# RT1064_Power.net
KiCad netlist of a schematic drawn in Altium Designer
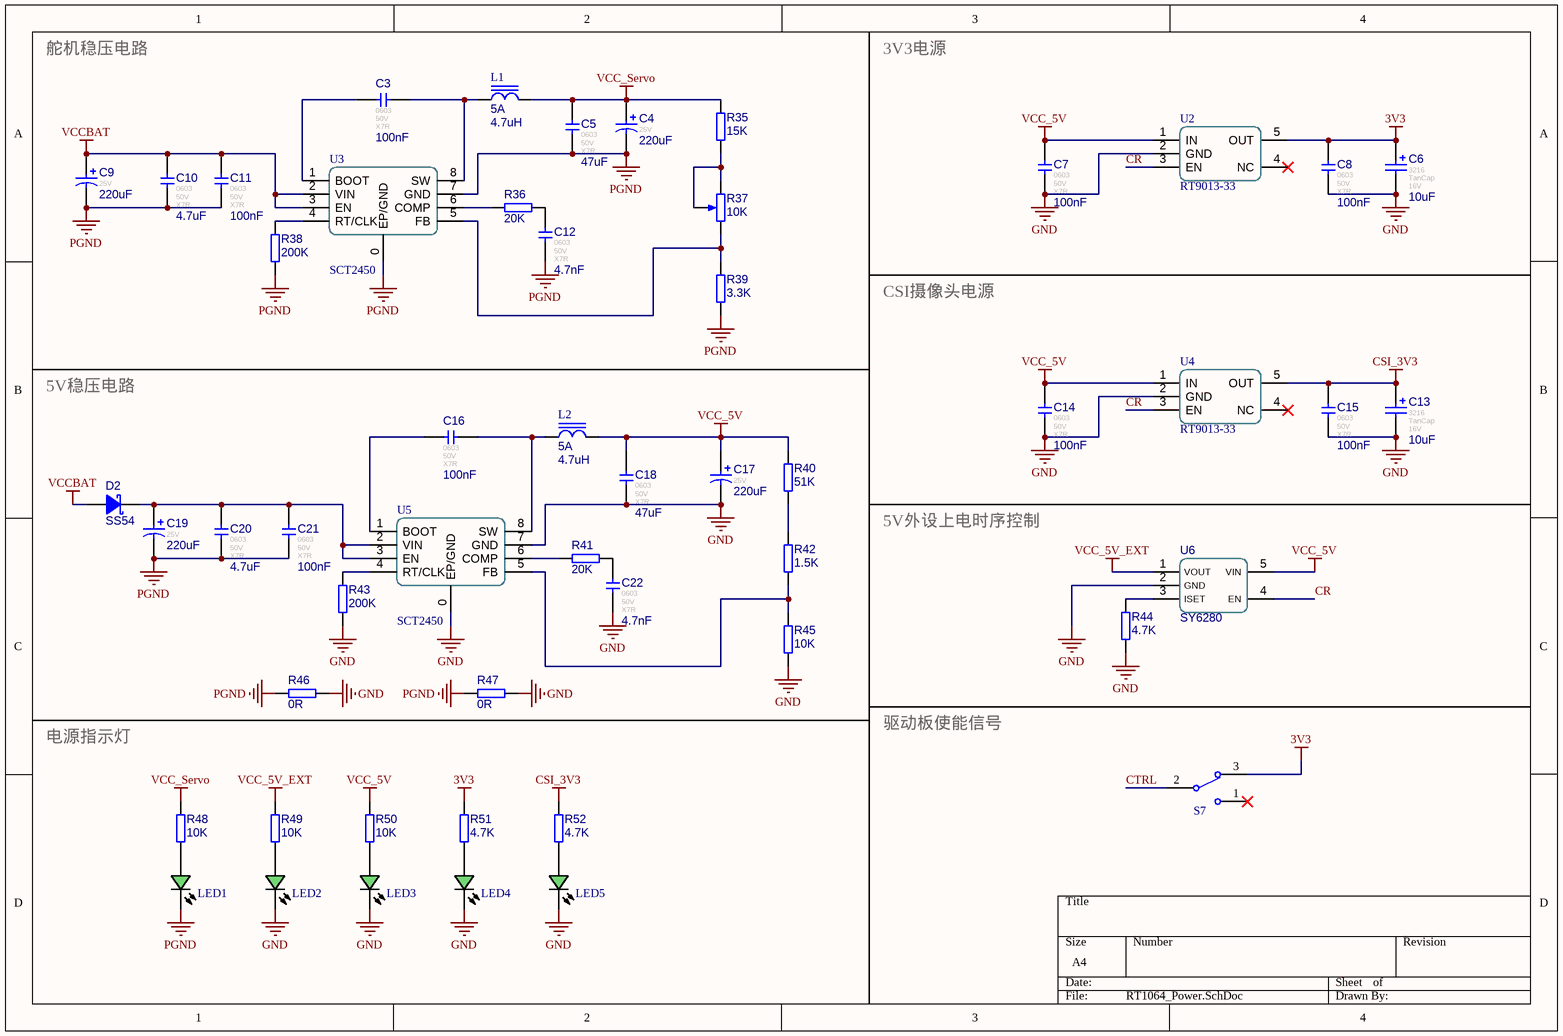
[diagram p0: RT1064_Power.SchDoc]

(export (version "E")
  (design (tool "Eeschema 10.0.6"))
  (components
    (comp (ref "C3")
      (value "100nF")
      (footprint "0603")
      (description "贴片瓷片电容; MLCC; 0603(1608);")
      (fields
        (field (name "VOLTAGE") "50V")
        (field (name "TYPE") "X7R")
        (field (name "Comment") "100nF 50V X7R")
      )
      (libsource (lib "RT1064_V1主板器件封装集成库") (part "100nF 0603 50V X7R"))
    )
    (comp (ref "C4")
      (value "220uF")
      (footprint "CAP-E-S 6.3")
      (description "贴片电解电容 220uF 25V 6.3x7.7")
      (fields (field (name "VOLTAGE") "25V") (field (name "Comment") "220uF 25V 铝电解"))
      (libsource (lib "RT1064_V1主板器件封装集成库") (part "E-S 220uF 25V 6.3x7.7"))
    )
    (comp (ref "C5")
      (value "47uF")
      (footprint "0603")
      (description "贴片瓷片电容; MLCC; 0603(1608);")
      (fields
        (field (name "VOLTAGE") "50V")
        (field (name "TYPE") "X7R")
        (field (name "Comment") "47uF 50V X7R")
      )
      (libsource (lib "RT1064_V1主板器件封装集成库") (part "100nF 0603 50V X7R"))
    )
    (comp (ref "C6")
      (value "10uF")
      (footprint "3216")
      (description "贴片钽电容 10uF 3216 16V")
      (fields
        (field (name "TYPE") "TanCap")
        (field (name "VOLTAGE") "16V")
        (field (name "Comment") "T-S 10uF 3216 16V")
      )
      (libsource (lib "RT1064_V1主板器件封装集成库") (part "T-S 10uF 3216 16V"))
    )
    (comp (ref "C7")
      (value "100nF")
      (footprint "0603")
      (description "贴片瓷片电容; MLCC; 0603(1608);")
      (fields
        (field (name "VOLTAGE") "50V")
        (field (name "TYPE") "X7R")
        (field (name "Comment") "100nF 50V X7R")
      )
      (libsource (lib "RT1064_V1主板器件封装集成库") (part "100nF 0603 50V X7R"))
    )
    (comp (ref "C8")
      (value "100nF")
      (footprint "0603")
      (description "贴片瓷片电容; MLCC; 0603(1608);")
      (fields
        (field (name "VOLTAGE") "50V")
        (field (name "TYPE") "X7R")
        (field (name "Comment") "100nF 50V X7R")
      )
      (libsource (lib "RT1064_V1主板器件封装集成库") (part "100nF 0603 50V X7R"))
    )
    (comp (ref "C9")
      (value "220uF")
      (footprint "CAP-E-S 6.3")
      (description "贴片电解电容 220uF 25V 6.3x7.7")
      (fields (field (name "VOLTAGE") "25V") (field (name "Comment") "220uF 25V 铝电解"))
      (libsource (lib "RT1064_V1主板器件封装集成库") (part "E-S 220uF 25V 6.3x7.7"))
    )
    (comp (ref "C10")
      (value "4.7uF")
      (footprint "0603")
      (description "贴片瓷片电容; MLCC; 0603(1608);")
      (fields
        (field (name "VOLTAGE") "50V")
        (field (name "TYPE") "X7R")
        (field (name "Comment") "4.7uF 50V X7R")
      )
      (libsource (lib "RT1064_V1主板器件封装集成库") (part "100nF 0603 50V X7R"))
    )
    (comp (ref "C11")
      (value "100nF")
      (footprint "0603")
      (description "贴片瓷片电容; MLCC; 0603(1608);")
      (fields
        (field (name "VOLTAGE") "50V")
        (field (name "TYPE") "X7R")
        (field (name "Comment") "100nF 50V X7R")
      )
      (libsource (lib "RT1064_V1主板器件封装集成库") (part "100nF 0603 50V X7R"))
    )
    (comp (ref "C12")
      (value "4.7nF")
      (footprint "0603")
      (description "贴片瓷片电容; MLCC; 0603(1608);")
      (fields
        (field (name "VOLTAGE") "50V")
        (field (name "TYPE") "X7R")
        (field (name "Comment") "4.7nF 50V X7R")
      )
      (libsource (lib "RT1064_V1主板器件封装集成库") (part "4.7nF 0603 50V X7R"))
    )
    (comp (ref "C13")
      (value "10uF")
      (footprint "3216")
      (description "贴片钽电容 10uF 3216 16V")
      (fields
        (field (name "TYPE") "TanCap")
        (field (name "VOLTAGE") "16V")
        (field (name "Comment") "T-S 10uF 3216 16V")
      )
      (libsource (lib "RT1064_V1主板器件封装集成库") (part "T-S 10uF 3216 16V"))
    )
    (comp (ref "C14")
      (value "100nF")
      (footprint "0603")
      (description "贴片瓷片电容; MLCC; 0603(1608);")
      (fields
        (field (name "VOLTAGE") "50V")
        (field (name "TYPE") "X7R")
        (field (name "Comment") "100nF 50V X7R")
      )
      (libsource (lib "RT1064_V1主板器件封装集成库") (part "100nF 0603 50V X7R"))
    )
    (comp (ref "C15")
      (value "100nF")
      (footprint "0603")
      (description "贴片瓷片电容; MLCC; 0603(1608);")
      (fields
        (field (name "VOLTAGE") "50V")
        (field (name "TYPE") "X7R")
        (field (name "Comment") "100nF 50V X7R")
      )
      (libsource (lib "RT1064_V1主板器件封装集成库") (part "100nF 0603 50V X7R"))
    )
    (comp (ref "C16")
      (value "100nF")
      (footprint "0603")
      (description "贴片瓷片电容; MLCC; 0603(1608);")
      (fields
        (field (name "VOLTAGE") "50V")
        (field (name "TYPE") "X7R")
        (field (name "Comment") "100nF 50V X7R")
      )
      (libsource (lib "RT1064_V1主板器件封装集成库") (part "100nF 0603 50V X7R"))
    )
    (comp (ref "C17")
      (value "220uF")
      (footprint "CAP-E-S 6.3")
      (description "贴片电解电容 220uF 25V 6.3x7.7")
      (fields (field (name "VOLTAGE") "25V") (field (name "Comment") "220uF 25V 铝电解"))
      (libsource (lib "RT1064_V1主板器件封装集成库") (part "E-S 220uF 25V 6.3x7.7"))
    )
    (comp (ref "C18")
      (value "47uF")
      (footprint "0603")
      (description "贴片瓷片电容; MLCC; 0603(1608);")
      (fields
        (field (name "VOLTAGE") "50V")
        (field (name "TYPE") "X7R")
        (field (name "Comment") "47uF 50V X7R")
      )
      (libsource (lib "RT1064_V1主板器件封装集成库") (part "100nF 0603 50V X7R"))
    )
    (comp (ref "C19")
      (value "220uF")
      (footprint "CAP-E-S 6.3")
      (description "贴片电解电容 220uF 25V 6.3x7.7")
      (fields (field (name "VOLTAGE") "25V") (field (name "Comment") "220uF 25V 铝电解"))
      (libsource (lib "RT1064_V1主板器件封装集成库") (part "E-S 220uF 25V 6.3x7.7"))
    )
    (comp (ref "C20")
      (value "4.7uF")
      (footprint "0603")
      (description "贴片瓷片电容; MLCC; 0603(1608);")
      (fields
        (field (name "VOLTAGE") "50V")
        (field (name "TYPE") "X7R")
        (field (name "Comment") "4.7uF 50V X7R")
      )
      (libsource (lib "RT1064_V1主板器件封装集成库") (part "100nF 0603 50V X7R"))
    )
    (comp (ref "C21")
      (value "100nF")
      (footprint "0603")
      (description "贴片瓷片电容; MLCC; 0603(1608);")
      (fields
        (field (name "VOLTAGE") "50V")
        (field (name "TYPE") "X7R")
        (field (name "Comment") "100nF 50V X7R")
      )
      (libsource (lib "RT1064_V1主板器件封装集成库") (part "100nF 0603 50V X7R"))
    )
    (comp (ref "C22")
      (value "4.7nF")
      (footprint "0603")
      (description "贴片瓷片电容; MLCC; 0603(1608);")
      (fields
        (field (name "VOLTAGE") "50V")
        (field (name "TYPE") "X7R")
        (field (name "Comment") "4.7nF 50V X7R")
      )
      (libsource (lib "RT1064_V1主板器件封装集成库") (part "4.7nF 0603 50V X7R"))
    )
    (comp (ref "D2")
      (value "SS54")
      (footprint "SMA-L[DO-214AC]")
      (description "SS54 肖特基二极管")
      (libsource (lib "RT1064_V1主板器件封装集成库") (part "SS54"))
    )
    (comp (ref "L1")
      (value "4.7uH")
      (footprint "0630 TPC 7*7*3")
      (description "功率电感")
      (fields
        (field (name "IMAX") "5A")
        (field (name "Comment") "4.7uH 5A")
        (field (name "PUBLISHER") "Altium Limited")
      )
      (libsource (lib "RT1064_V1主板器件封装集成库") (part "Ind-Power"))
    )
    (comp (ref "L2")
      (value "4.7uH")
      (footprint "0630 TPC 7*7*3")
      (description "功率电感")
      (fields
        (field (name "IMAX") "5A")
        (field (name "Comment") "4.7uH 5A")
        (field (name "PUBLISHER") "Altium Limited")
      )
      (libsource (lib "RT1064_V1主板器件封装集成库") (part "Ind-Power"))
    )
    (comp (ref "LED1")
      (value "翠绿贴片LED")
      (footprint "LEDC1608(0603)-L")
      (fields (field (name "PUBLISHER") "Altium Limited"))
      (libsource (lib "RT1064_V1主板器件封装集成库") (part "LED Chip Green"))
    )
    (comp (ref "LED2")
      (value "翠绿贴片LED")
      (footprint "LEDC1608(0603)-L")
      (fields (field (name "PUBLISHER") "Altium Limited"))
      (libsource (lib "RT1064_V1主板器件封装集成库") (part "LED Chip Green"))
    )
    (comp (ref "LED3")
      (value "翠绿贴片LED")
      (footprint "LEDC1608(0603)-L")
      (fields (field (name "PUBLISHER") "Altium Limited"))
      (libsource (lib "RT1064_V1主板器件封装集成库") (part "LED Chip Green"))
    )
    (comp (ref "LED4")
      (value "翠绿贴片LED")
      (footprint "LEDC1608(0603)-L")
      (fields (field (name "PUBLISHER") "Altium Limited"))
      (libsource (lib "RT1064_V1主板器件封装集成库") (part "LED Chip Green"))
    )
    (comp (ref "LED5")
      (value "翠绿贴片LED")
      (footprint "LEDC1608(0603)-L")
      (fields (field (name "PUBLISHER") "Altium Limited"))
      (libsource (lib "RT1064_V1主板器件封装集成库") (part "LED Chip Green"))
    )
    (comp (ref "R35")
      (value "15K")
      (footprint "RESC1608[0603]S-L")
      (description "贴片电阻")
      (fields (field (name "POWER") "1/8W") (field (name "TOLERANCE") "±1%"))
      (libsource (lib "RT1064_V1主板器件封装集成库") (part "Res-Chip"))
    )
    (comp (ref "R36")
      (value "20K")
      (footprint "RESC1608[0603]S-L")
      (description "贴片电阻")
      (fields (field (name "POWER") "1/8W") (field (name "TOLERANCE") "±1%"))
      (libsource (lib "RT1064_V1主板器件封装集成库") (part "Res-Chip"))
    )
    (comp (ref "R37")
      (value "10K")
      (footprint "RESPOT3296W")
      (description "可调电阻")
      (libsource (lib "RT1064_V1主板器件封装集成库") (part "Res-Adj-3p"))
    )
    (comp (ref "R38")
      (value "200K")
      (footprint "RESC1608[0603]S-L")
      (description "贴片电阻")
      (fields (field (name "POWER") "1/8W") (field (name "TOLERANCE") "±1%"))
      (libsource (lib "RT1064_V1主板器件封装集成库") (part "Res-Chip"))
    )
    (comp (ref "R39")
      (value "3.3K")
      (footprint "RESC1608[0603]S-L")
      (description "贴片电阻")
      (fields (field (name "POWER") "1/8W") (field (name "TOLERANCE") "±1%"))
      (libsource (lib "RT1064_V1主板器件封装集成库") (part "Res-Chip"))
    )
    (comp (ref "R40")
      (value "51K")
      (footprint "RESC1608[0603]S-L")
      (description "贴片电阻")
      (fields (field (name "POWER") "1/8W") (field (name "TOLERANCE") "±1%"))
      (libsource (lib "RT1064_V1主板器件封装集成库") (part "Res-Chip"))
    )
    (comp (ref "R41")
      (value "20K")
      (footprint "RESC1608[0603]S-L")
      (description "贴片电阻")
      (fields (field (name "POWER") "1/8W") (field (name "TOLERANCE") "±1%"))
      (libsource (lib "RT1064_V1主板器件封装集成库") (part "Res-Chip"))
    )
    (comp (ref "R42")
      (value "1.5K")
      (footprint "RESC1608[0603]S-L")
      (description "贴片电阻")
      (fields (field (name "POWER") "1/8W") (field (name "TOLERANCE") "±1%"))
      (libsource (lib "RT1064_V1主板器件封装集成库") (part "Res-Chip"))
    )
    (comp (ref "R43")
      (value "200K")
      (footprint "RESC1608[0603]S-L")
      (description "贴片电阻")
      (fields (field (name "POWER") "1/8W") (field (name "TOLERANCE") "±1%"))
      (libsource (lib "RT1064_V1主板器件封装集成库") (part "Res-Chip"))
    )
    (comp (ref "R44")
      (value "4.7K")
      (footprint "RESC1608[0603]S-L")
      (description "贴片电阻")
      (fields (field (name "POWER") "1/8W") (field (name "TOLERANCE") "±1%"))
      (libsource (lib "RT1064_V1主板器件封装集成库") (part "Res-Chip"))
    )
    (comp (ref "R45")
      (value "10K")
      (footprint "RESC1608[0603]S-L")
      (description "贴片电阻")
      (fields (field (name "POWER") "1/8W") (field (name "TOLERANCE") "±1%"))
      (libsource (lib "RT1064_V1主板器件封装集成库") (part "Res-Chip"))
    )
    (comp (ref "R46")
      (value "0R")
      (footprint "RESC1608[0603]S-L")
      (description "贴片电阻")
      (fields (field (name "POWER") "1/8W") (field (name "TOLERANCE") "±1%"))
      (libsource (lib "RT1064_V1主板器件封装集成库") (part "Res-Chip_1"))
    )
    (comp (ref "R47")
      (value "0R")
      (footprint "RESC1608[0603]S-L")
      (description "贴片电阻")
      (fields (field (name "POWER") "1/8W") (field (name "TOLERANCE") "±1%"))
      (libsource (lib "RT1064_V1主板器件封装集成库") (part "Res-Chip_1"))
    )
    (comp (ref "R48")
      (value "10K")
      (footprint "RESC1608[0603]S-L")
      (description "贴片电阻")
      (fields (field (name "POWER") "1/8W") (field (name "TOLERANCE") "±1%"))
      (libsource (lib "RT1064_V1主板器件封装集成库") (part "Res-Chip"))
    )
    (comp (ref "R49")
      (value "10K")
      (footprint "RESC1608[0603]S-L")
      (description "贴片电阻")
      (fields (field (name "POWER") "1/8W") (field (name "TOLERANCE") "±1%"))
      (libsource (lib "RT1064_V1主板器件封装集成库") (part "Res-Chip"))
    )
    (comp (ref "R50")
      (value "10K")
      (footprint "RESC1608[0603]S-L")
      (description "贴片电阻")
      (fields (field (name "POWER") "1/8W") (field (name "TOLERANCE") "±1%"))
      (libsource (lib "RT1064_V1主板器件封装集成库") (part "Res-Chip"))
    )
    (comp (ref "R51")
      (value "4.7K")
      (footprint "RESC1608[0603]S-L")
      (description "贴片电阻")
      (fields (field (name "POWER") "1/8W") (field (name "TOLERANCE") "±1%"))
      (libsource (lib "RT1064_V1主板器件封装集成库") (part "Res-Chip"))
    )
    (comp (ref "R52")
      (value "4.7K")
      (footprint "RESC1608[0603]S-L")
      (description "贴片电阻")
      (fields (field (name "POWER") "1/8W") (field (name "TOLERANCE") "±1%"))
      (libsource (lib "RT1064_V1主板器件封装集成库") (part "Res-Chip"))
    )
    (comp (ref "S7")
      (value "SW-SPDT")
      (footprint "SS-12F23")
      (description "单刀双掷开关 3脚船型、钮子、拨动开关 SPDT Subminiature Toggle Switch")
      (fields (field (name "PUBLISHER") "Altium Limited"))
      (libsource (lib "RT1064_V1主板器件封装集成库") (part "SW-SPDT"))
    )
    (comp (ref "U2")
      (value "RT9013-33")
      (footprint "SOT-23-5")
      (description "3.3V 500mA SOT-23-5 LDO")
      (libsource (lib "RT1064_V1主板器件封装集成库") (part "RT9013-33"))
    )
    (comp (ref "U3")
      (value "SCT2450")
      (footprint "SOP-8E")
      (libsource (lib "RT1064_V1主板器件封装集成库") (part "SCT2450"))
    )
    (comp (ref "U4")
      (value "RT9013-33")
      (footprint "SOT-23-5")
      (description "3.3V 500mA SOT-23-5 LDO")
      (libsource (lib "RT1064_V1主板器件封装集成库") (part "RT9013-33"))
    )
    (comp (ref "U5")
      (value "SCT2450")
      (footprint "SOP-8E")
      (libsource (lib "RT1064_V1主板器件封装集成库") (part "SCT2450"))
    )
    (comp (ref "U6")
      (value "SY6280")
      (footprint "SOT-23-5")
      (description "SY6280 2A 限额配电开关")
      (libsource (lib "RT1064_V1主板器件封装集成库") (part "SY6280"))
    )
  )
  (nets
    (net (code "1") (name "/CR") (class "Default")
      (node (ref "U2") (pin "3") (pinfunction "EN_3") (pintype "passive"))
      (node (ref "U4") (pin "3") (pinfunction "EN_3") (pintype "passive"))
      (node (ref "U6") (pin "4") (pinfunction "EN_4") (pintype "passive"))
    )
    (net (code "2") (name "/CTRL") (class "Default") (node (ref "S7") (pin "2") (pintype "passive")))
    (net (code "3") (name "3V3") (class "Default")
      (node (ref "C6") (pin "1") (pinfunction "1_1") (pintype "passive"))
      (node (ref "C8") (pin "2") (pinfunction "2_2") (pintype "passive"))
      (node (ref "R51") (pin "2") (pinfunction "2_2") (pintype "passive"))
      (node (ref "S7") (pin "3") (pintype "passive"))
      (node (ref "U2") (pin "5") (pinfunction "OUT_5") (pintype "passive"))
    )
    (net (code "4") (name "CSI_3V3") (class "Default")
      (node (ref "C13") (pin "1") (pinfunction "1_1") (pintype "passive"))
      (node (ref "C15") (pin "2") (pinfunction "2_2") (pintype "passive"))
      (node (ref "R52") (pin "2") (pinfunction "2_2") (pintype "passive"))
      (node (ref "U4") (pin "5") (pinfunction "OUT_5") (pintype "passive"))
    )
    (net (code "5") (name "GND") (class "Default")
      (node (ref "C13") (pin "2") (pinfunction "2_2") (pintype "passive"))
      (node (ref "C14") (pin "1") (pinfunction "1_1") (pintype "passive"))
      (node (ref "C15") (pin "1") (pinfunction "1_1") (pintype "passive"))
      (node (ref "C17") (pin "2") (pinfunction "2_2") (pintype "passive"))
      (node (ref "C18") (pin "1") (pinfunction "1_1") (pintype "passive"))
      (node (ref "C22") (pin "1") (pinfunction "1_1") (pintype "passive"))
      (node (ref "C6") (pin "2") (pinfunction "2_2") (pintype "passive"))
      (node (ref "C7") (pin "1") (pinfunction "1_1") (pintype "passive"))
      (node (ref "C8") (pin "1") (pinfunction "1_1") (pintype "passive"))
      (node (ref "LED2") (pin "C") (pinfunction "C_C") (pintype "passive"))
      (node (ref "LED3") (pin "C") (pinfunction "C_C") (pintype "passive"))
      (node (ref "LED4") (pin "C") (pinfunction "C_C") (pintype "passive"))
      (node (ref "LED5") (pin "C") (pinfunction "C_C") (pintype "passive"))
      (node (ref "R43") (pin "1") (pinfunction "1_1") (pintype "passive"))
      (node (ref "R44") (pin "1") (pinfunction "1_1") (pintype "passive"))
      (node (ref "R45") (pin "1") (pinfunction "1_1") (pintype "passive"))
      (node (ref "R46") (pin "2") (pinfunction "2_2") (pintype "passive"))
      (node (ref "R47") (pin "2") (pinfunction "2_2") (pintype "passive"))
      (node (ref "U2") (pin "2") (pinfunction "GND_2") (pintype "passive"))
      (node (ref "U4") (pin "2") (pinfunction "GND_2") (pintype "passive"))
      (node (ref "U5") (pin "0") (pinfunction "EP/GND_0") (pintype "passive"))
      (node (ref "U5") (pin "7") (pinfunction "GND_7") (pintype "passive"))
      (node (ref "U6") (pin "2") (pinfunction "GND_2") (pintype "passive"))
    )
    (net (code "6") (name "Net-(C12-Pad2)") (class "Default")
      (node (ref "C12") (pin "2") (pinfunction "2_2") (pintype "passive"))
      (node (ref "R36") (pin "1") (pinfunction "1_1") (pintype "passive"))
    )
    (net (code "7") (name "Net-(C22-Pad2)") (class "Default")
      (node (ref "C22") (pin "2") (pinfunction "2_2") (pintype "passive"))
      (node (ref "R41") (pin "1") (pinfunction "1_1") (pintype "passive"))
    )
    (net (code "8") (name "Net-(LED1-PadA)") (class "Default")
      (node (ref "LED1") (pin "A") (pinfunction "A_A") (pintype "passive"))
      (node (ref "R48") (pin "1") (pinfunction "1_1") (pintype "passive"))
    )
    (net (code "9") (name "Net-(LED2-PadA)") (class "Default")
      (node (ref "LED2") (pin "A") (pinfunction "A_A") (pintype "passive"))
      (node (ref "R49") (pin "1") (pinfunction "1_1") (pintype "passive"))
    )
    (net (code "10") (name "Net-(LED3-PadA)") (class "Default")
      (node (ref "LED3") (pin "A") (pinfunction "A_A") (pintype "passive"))
      (node (ref "R50") (pin "1") (pinfunction "1_1") (pintype "passive"))
    )
    (net (code "11") (name "Net-(LED4-PadA)") (class "Default")
      (node (ref "LED4") (pin "A") (pinfunction "A_A") (pintype "passive"))
      (node (ref "R51") (pin "1") (pinfunction "1_1") (pintype "passive"))
    )
    (net (code "12") (name "Net-(LED5-PadA)") (class "Default")
      (node (ref "LED5") (pin "A") (pinfunction "A_A") (pintype "passive"))
      (node (ref "R52") (pin "1") (pinfunction "1_1") (pintype "passive"))
    )
    (net (code "13") (name "Net-(R37-BOT)") (class "Default")
      (node (ref "R37") (pin "2") (pinfunction "BOT_2") (pintype "passive"))
      (node (ref "R39") (pin "2") (pinfunction "2_2") (pintype "passive"))
      (node (ref "U3") (pin "5") (pinfunction "FB_5") (pintype "passive"))
    )
    (net (code "14") (name "Net-(R37-TOP)") (class "Default")
      (node (ref "R35") (pin "1") (pinfunction "1_1") (pintype "passive"))
      (node (ref "R37") (pin "1") (pinfunction "TOP_1") (pintype "passive"))
      (node (ref "R37") (pin "ADJ") (pinfunction "ADJ_ADJ") (pintype "passive"))
    )
    (net (code "15") (name "Net-(R40-Pad1)") (class "Default")
      (node (ref "R40") (pin "1") (pinfunction "1_1") (pintype "passive"))
      (node (ref "R42") (pin "2") (pinfunction "2_2") (pintype "passive"))
    )
    (net (code "16") (name "Net-(U3-BOOT)") (class "Default")
      (node (ref "C3") (pin "2") (pinfunction "2_2") (pintype "passive"))
      (node (ref "U3") (pin "1") (pinfunction "BOOT_1") (pintype "passive"))
    )
    (net (code "17") (name "Net-(U3-COMP)") (class "Default")
      (node (ref "R36") (pin "2") (pinfunction "2_2") (pintype "passive"))
      (node (ref "U3") (pin "6") (pinfunction "COMP_6") (pintype "passive"))
    )
    (net (code "18") (name "Net-(U3-RT{slash}CLK)") (class "Default")
      (node (ref "R38") (pin "2") (pinfunction "2_2") (pintype "passive"))
      (node (ref "U3") (pin "4") (pinfunction "RT/CLK_4") (pintype "passive"))
    )
    (net (code "19") (name "Net-(U3-SW)") (class "Default")
      (node (ref "C3") (pin "1") (pinfunction "1_1") (pintype "passive"))
      (node (ref "L1") (pin "1") (pinfunction "1_1") (pintype "passive"))
      (node (ref "U3") (pin "8") (pinfunction "SW_8") (pintype "passive"))
    )
    (net (code "20") (name "Net-(U5-BOOT)") (class "Default")
      (node (ref "C16") (pin "2") (pinfunction "2_2") (pintype "passive"))
      (node (ref "U5") (pin "1") (pinfunction "BOOT_1") (pintype "passive"))
    )
    (net (code "21") (name "Net-(U5-COMP)") (class "Default")
      (node (ref "R41") (pin "2") (pinfunction "2_2") (pintype "passive"))
      (node (ref "U5") (pin "6") (pinfunction "COMP_6") (pintype "passive"))
    )
    (net (code "22") (name "Net-(U5-EN)") (class "Default")
      (node (ref "C19") (pin "1") (pinfunction "1_1") (pintype "passive"))
      (node (ref "C20") (pin "2") (pinfunction "2_2") (pintype "passive"))
      (node (ref "C21") (pin "2") (pinfunction "2_2") (pintype "passive"))
      (node (ref "D2") (pin "K") (pinfunction "K_K") (pintype "passive"))
      (node (ref "U5") (pin "2") (pinfunction "VIN_2") (pintype "passive"))
      (node (ref "U5") (pin "3") (pinfunction "EN_3") (pintype "passive"))
    )
    (net (code "23") (name "Net-(U5-FB)") (class "Default")
      (node (ref "R42") (pin "1") (pinfunction "1_1") (pintype "passive"))
      (node (ref "R45") (pin "2") (pinfunction "2_2") (pintype "passive"))
      (node (ref "U5") (pin "5") (pinfunction "FB_5") (pintype "passive"))
    )
    (net (code "24") (name "Net-(U5-RT{slash}CLK)") (class "Default")
      (node (ref "R43") (pin "2") (pinfunction "2_2") (pintype "passive"))
      (node (ref "U5") (pin "4") (pinfunction "RT/CLK_4") (pintype "passive"))
    )
    (net (code "25") (name "Net-(U5-SW)") (class "Default")
      (node (ref "C16") (pin "1") (pinfunction "1_1") (pintype "passive"))
      (node (ref "L2") (pin "1") (pinfunction "1_1") (pintype "passive"))
      (node (ref "U5") (pin "8") (pinfunction "SW_8") (pintype "passive"))
    )
    (net (code "26") (name "Net-(U6-ISET)") (class "Default")
      (node (ref "R44") (pin "2") (pinfunction "2_2") (pintype "passive"))
      (node (ref "U6") (pin "3") (pinfunction "ISET_3") (pintype "passive"))
    )
    (net (code "27") (name "PGND") (class "Default")
      (node (ref "C10") (pin "1") (pinfunction "1_1") (pintype "passive"))
      (node (ref "C11") (pin "1") (pinfunction "1_1") (pintype "passive"))
      (node (ref "C12") (pin "1") (pinfunction "1_1") (pintype "passive"))
      (node (ref "C19") (pin "2") (pinfunction "2_2") (pintype "passive"))
      (node (ref "C20") (pin "1") (pinfunction "1_1") (pintype "passive"))
      (node (ref "C21") (pin "1") (pinfunction "1_1") (pintype "passive"))
      (node (ref "C4") (pin "2") (pinfunction "2_2") (pintype "passive"))
      (node (ref "C5") (pin "1") (pinfunction "1_1") (pintype "passive"))
      (node (ref "C9") (pin "2") (pinfunction "2_2") (pintype "passive"))
      (node (ref "LED1") (pin "C") (pinfunction "C_C") (pintype "passive"))
      (node (ref "R38") (pin "1") (pinfunction "1_1") (pintype "passive"))
      (node (ref "R39") (pin "1") (pinfunction "1_1") (pintype "passive"))
      (node (ref "R46") (pin "1") (pinfunction "1_1") (pintype "passive"))
      (node (ref "R47") (pin "1") (pinfunction "1_1") (pintype "passive"))
      (node (ref "U3") (pin "0") (pinfunction "EP/GND_0") (pintype "passive"))
      (node (ref "U3") (pin "7") (pinfunction "GND_7") (pintype "passive"))
    )
    (net (code "28") (name "VCCBAT") (class "Default")
      (node (ref "C10") (pin "2") (pinfunction "2_2") (pintype "passive"))
      (node (ref "C11") (pin "2") (pinfunction "2_2") (pintype "passive"))
      (node (ref "C9") (pin "1") (pinfunction "1_1") (pintype "passive"))
      (node (ref "D2") (pin "A") (pinfunction "A_A") (pintype "passive"))
      (node (ref "U3") (pin "2") (pinfunction "VIN_2") (pintype "passive"))
      (node (ref "U3") (pin "3") (pinfunction "EN_3") (pintype "passive"))
    )
    (net (code "29") (name "VCC_5V") (class "Default")
      (node (ref "C14") (pin "2") (pinfunction "2_2") (pintype "passive"))
      (node (ref "C17") (pin "1") (pinfunction "1_1") (pintype "passive"))
      (node (ref "C18") (pin "2") (pinfunction "2_2") (pintype "passive"))
      (node (ref "C7") (pin "2") (pinfunction "2_2") (pintype "passive"))
      (node (ref "L2") (pin "2") (pinfunction "2_2") (pintype "passive"))
      (node (ref "R40") (pin "2") (pinfunction "2_2") (pintype "passive"))
      (node (ref "R50") (pin "2") (pinfunction "2_2") (pintype "passive"))
      (node (ref "U2") (pin "1") (pinfunction "IN_1") (pintype "passive"))
      (node (ref "U4") (pin "1") (pinfunction "IN_1") (pintype "passive"))
      (node (ref "U6") (pin "5") (pinfunction "VIN_5") (pintype "passive"))
    )
    (net (code "30") (name "VCC_5V_EXT") (class "Default")
      (node (ref "R49") (pin "2") (pinfunction "2_2") (pintype "passive"))
      (node (ref "U6") (pin "1") (pinfunction "VOUT_1") (pintype "passive"))
    )
    (net (code "31") (name "VCC_Servo") (class "Default")
      (node (ref "C4") (pin "1") (pinfunction "1_1") (pintype "passive"))
      (node (ref "C5") (pin "2") (pinfunction "2_2") (pintype "passive"))
      (node (ref "L1") (pin "2") (pinfunction "2_2") (pintype "passive"))
      (node (ref "R35") (pin "2") (pinfunction "2_2") (pintype "passive"))
      (node (ref "R48") (pin "2") (pinfunction "2_2") (pintype "passive"))
    )
    (net (code "32") (name "unconnected-(S7-Pad1)") (class "Default")
      (node (ref "S7") (pin "1") (pintype "passive+no_connect"))
    )
    (net (code "33") (name "unconnected-(U2-NC-Pad4)") (class "Default")
      (node (ref "U2") (pin "4") (pinfunction "NC_4") (pintype "passive+no_connect"))
    )
    (net (code "34") (name "unconnected-(U4-NC-Pad4)") (class "Default")
      (node (ref "U4") (pin "4") (pinfunction "NC_4") (pintype "passive+no_connect"))
    )
  )
)
